# SCH_RoboFootball_2024-06-07.net
KiCad netlist of a schematic drawn in EasyEDA
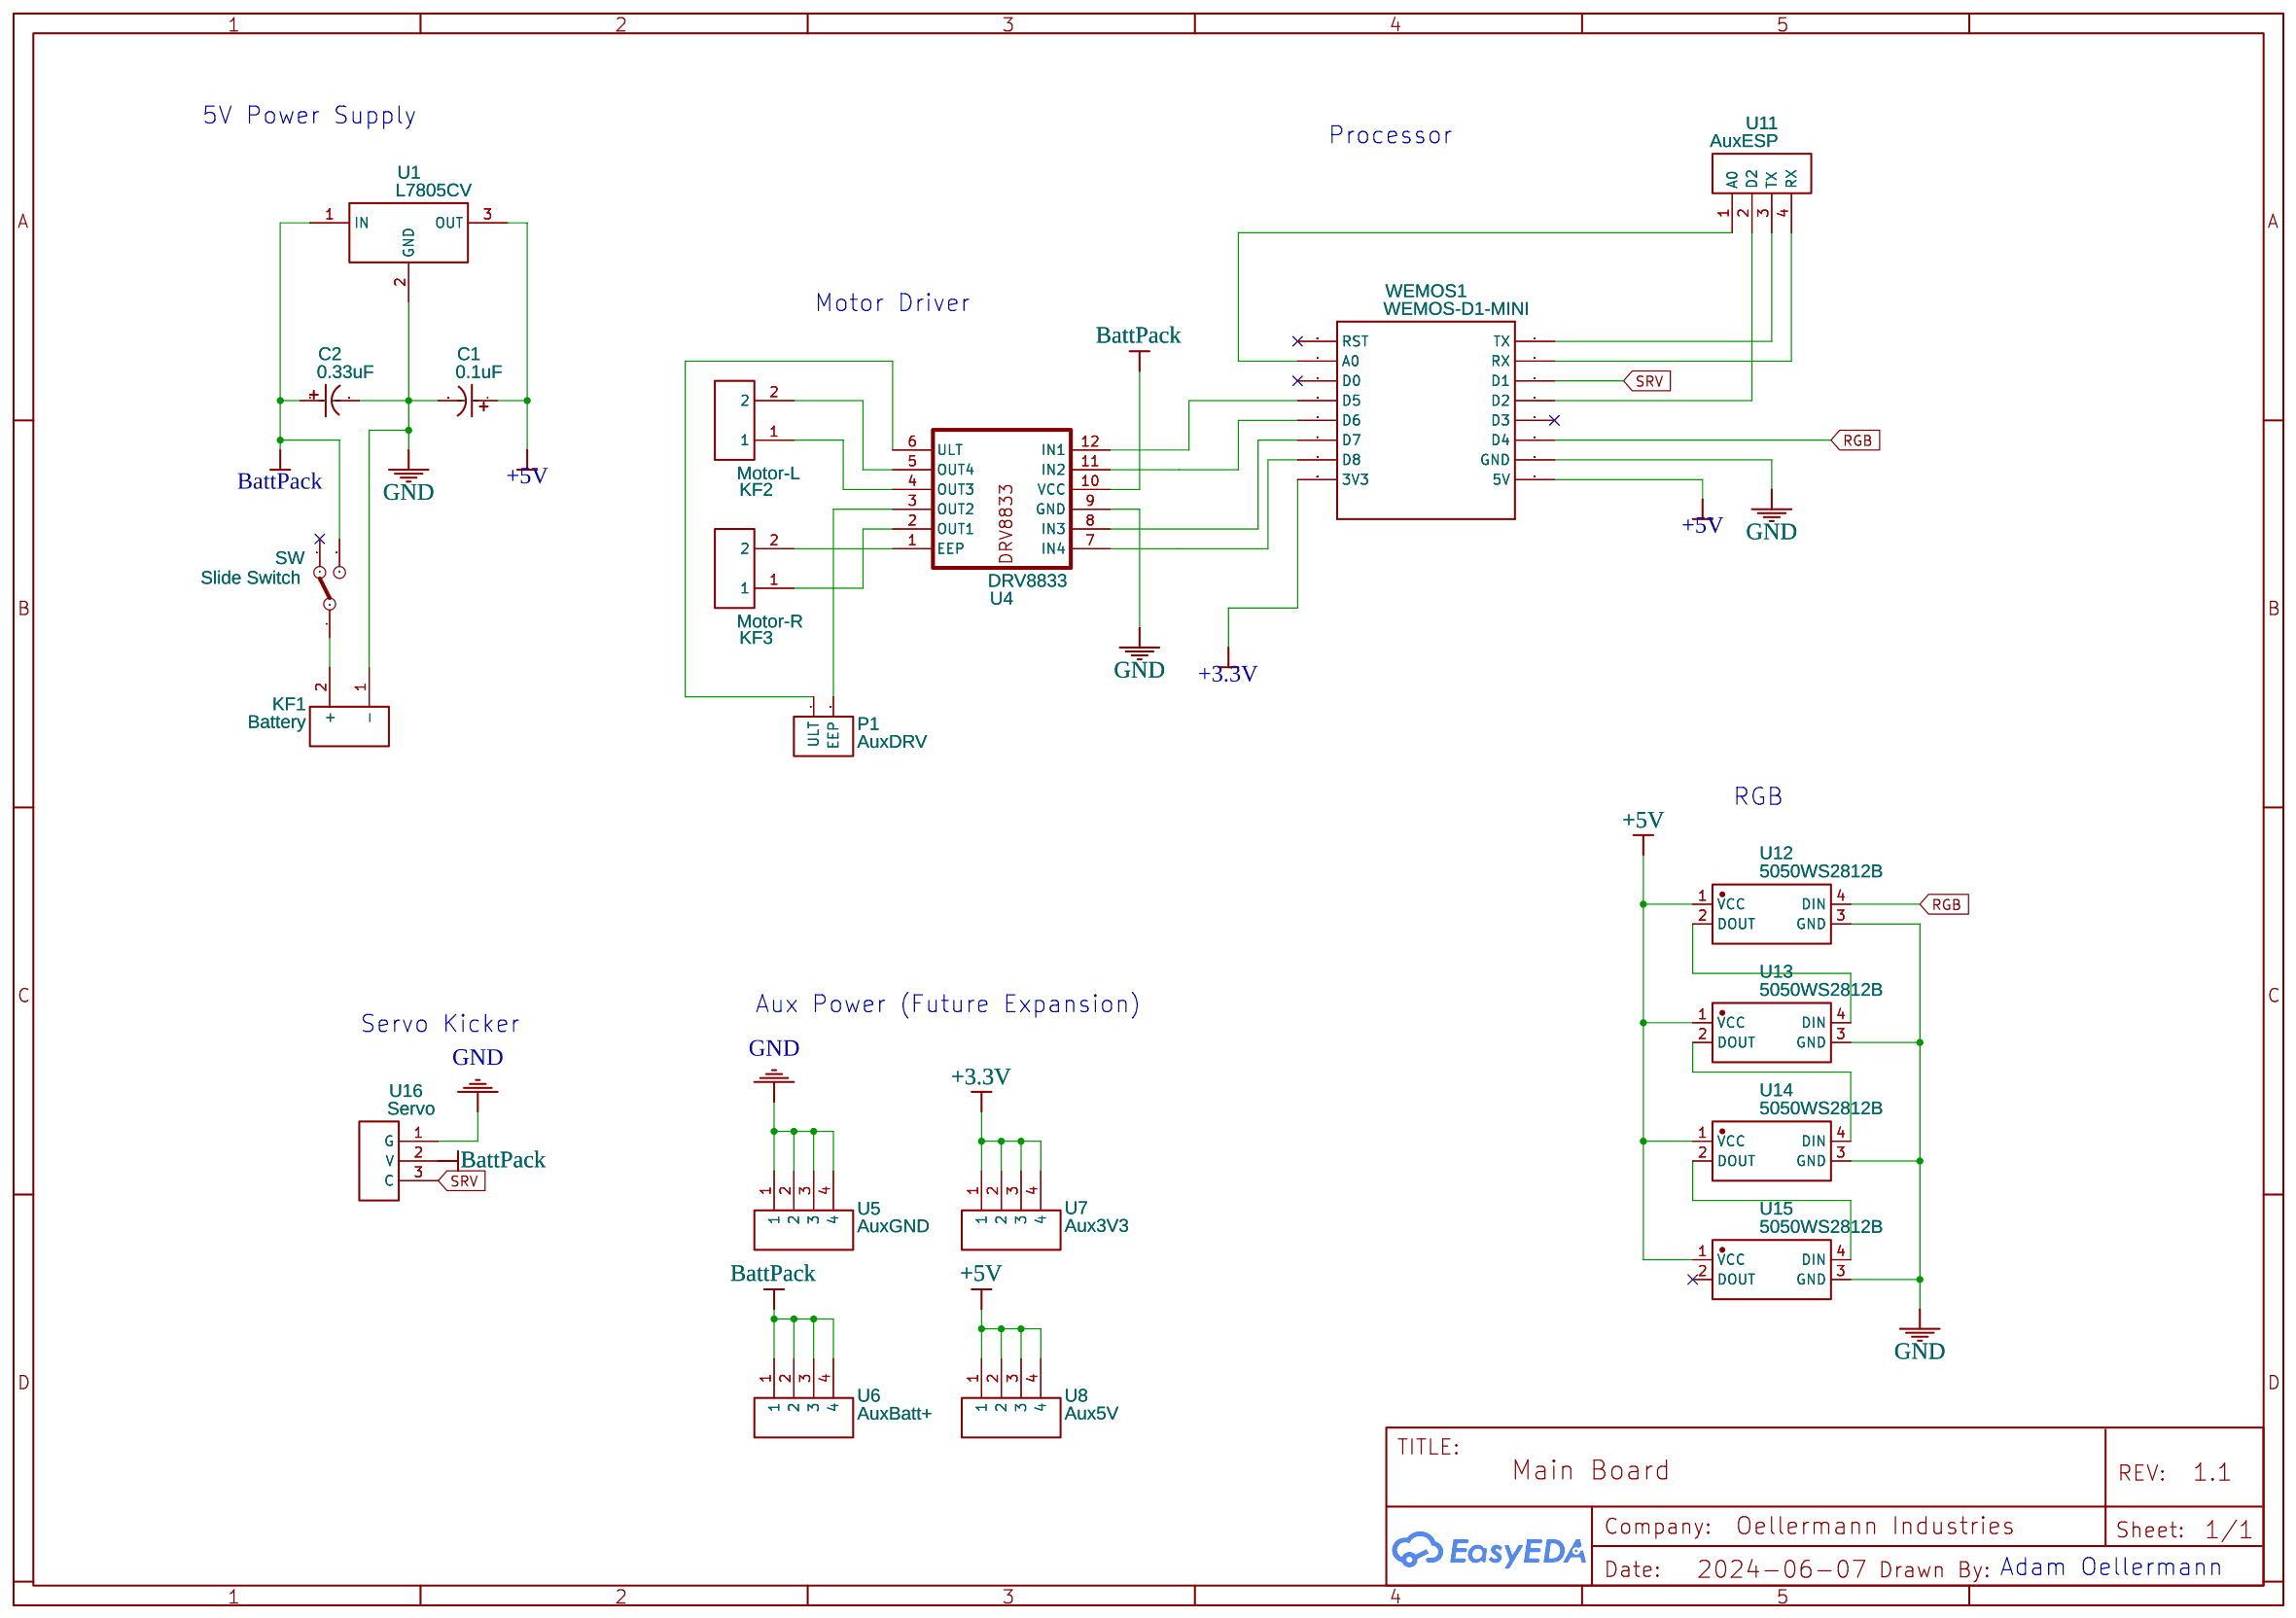
[diagram p0: schematic sheet]

(export (version "E")
  (design (tool "Eeschema 10.0.6"))
  (components
    (comp (ref "C1")
      (value "0.1uF")
      (fields
        (field (name "BOM_Manufacturer Part") "0.1uF 50V 4*7")
        (field (name "BOM_Supplier Part") "C45664")
      )
      (libsource (lib "") (part "0.1uF 50V 4*7"))
    )
    (comp (ref "C2")
      (value "0.33uF")
      (fields
        (field (name "BOM_Manufacturer Part") "0.33uF 50V 4*7")
        (field (name "BOM_Supplier Part") "C47875")
      )
      (libsource (lib "") (part "0.33uF 50V 4*7"))
    )
    (comp (ref "KF1") (value "Battery") (libsource (lib "") (part "K-301-2P")))
    (comp (ref "KF2") (value "Motor-L") (libsource (lib "") (part "K-301-2P_1")))
    (comp (ref "KF3") (value "Motor-R") (libsource (lib "") (part "K-301-2P_1")))
    (comp (ref "P1")
      (value "AuxDRV")
      (fields
        (field (name "BOM_Manufacturer Part") "2.54-1*2PFemale")
        (field (name "BOM_Supplier Part") "C49661")
      )
      (libsource (lib "") (part "Header-Female-2.54_1x2"))
    )
    (comp (ref "SW")
      (value "Slide Switch")
      (fields (field (name "BOM_Manufacturer Part") "Switch SPDT"))
      (libsource (lib "") (part "Slide Switch"))
    )
    (comp (ref "U1")
      (value "L7805CV")
      (fields (field (name "BOM_Supplier Part") "C111887"))
      (libsource (lib "") (part "L7805CV"))
    )
    (comp (ref "U4") (value "DRV8833") (libsource (lib "") (part "DRV8833 (NO ORIGINAL)")))
    (comp (ref "U5")
      (value "AuxGND")
      (fields (field (name "BOM_Supplier Part") "undefined"))
      (libsource (lib "") (part "PINHEADER1X4"))
    )
    (comp (ref "U6")
      (value "AuxBatt+")
      (fields (field (name "BOM_Supplier Part") "undefined"))
      (libsource (lib "") (part "PINHEADER1X4"))
    )
    (comp (ref "U7")
      (value "Aux3V3")
      (fields (field (name "BOM_Supplier Part") "undefined"))
      (libsource (lib "") (part "PINHEADER1X4"))
    )
    (comp (ref "U8")
      (value "Aux5V")
      (fields (field (name "BOM_Supplier Part") "undefined"))
      (libsource (lib "") (part "PINHEADER1X4"))
    )
    (comp (ref "U11")
      (value "AuxESP")
      (fields (field (name "BOM_Supplier Part") "undefined"))
      (libsource (lib "") (part "PINHEADER1X4_1"))
    )
    (comp (ref "U12")
      (value "5050WS2812B")
      (fields (field (name "BOM_Supplier Part") "C2874876"))
      (libsource (lib "") (part "5050WS2812B"))
    )
    (comp (ref "U13")
      (value "5050WS2812B")
      (fields (field (name "BOM_Supplier Part") "C2874876"))
      (libsource (lib "") (part "5050WS2812B"))
    )
    (comp (ref "U14")
      (value "5050WS2812B")
      (fields (field (name "BOM_Supplier Part") "C2874876"))
      (libsource (lib "") (part "5050WS2812B"))
    )
    (comp (ref "U15")
      (value "5050WS2812B")
      (fields (field (name "BOM_Supplier Part") "C2874876"))
      (libsource (lib "") (part "5050WS2812B"))
    )
    (comp (ref "U16")
      (value "Servo")
      (fields (field (name "BOM_Manufacturer Part") "Pin_Header_2"))
      (libsource (lib "") (part "PINHEADER1X3"))
    )
    (comp (ref "WEMOS1") (value "WEMOS-D1-MINI") (libsource (lib "") (part "WEMOS-D1-MINI")))
  )
  (nets
    (net (code "1") (name "+3.3V") (class "Default")
      (node (ref "U7") (pin "1") (pinfunction "1_1") (pintype "unspecified"))
      (node (ref "U7") (pin "2") (pinfunction "2_2") (pintype "unspecified"))
      (node (ref "U7") (pin "3") (pinfunction "3_3") (pintype "unspecified"))
      (node (ref "U7") (pin "4") (pinfunction "4_4") (pintype "unspecified"))
      (node (ref "WEMOS1") (pin "3V3") (pinfunction "3V3_3V3") (pintype "unspecified"))
    )
    (net (code "2") (name "+5V") (class "Default")
      (node (ref "C1") (pin "1") (pinfunction "1_1") (pintype "input"))
      (node (ref "U1") (pin "3") (pinfunction "OUT_3") (pintype "passive"))
      (node (ref "U12") (pin "1") (pinfunction "VCC_1") (pintype "unspecified"))
      (node (ref "U13") (pin "1") (pinfunction "VCC_1") (pintype "unspecified"))
      (node (ref "U14") (pin "1") (pinfunction "VCC_1") (pintype "unspecified"))
      (node (ref "U15") (pin "1") (pinfunction "VCC_1") (pintype "unspecified"))
      (node (ref "U8") (pin "1") (pinfunction "1_1") (pintype "unspecified"))
      (node (ref "U8") (pin "2") (pinfunction "2_2") (pintype "unspecified"))
      (node (ref "U8") (pin "3") (pinfunction "3_3") (pintype "unspecified"))
      (node (ref "U8") (pin "4") (pinfunction "4_4") (pintype "unspecified"))
      (node (ref "WEMOS1") (pin "5V") (pinfunction "5V_5V") (pintype "unspecified"))
    )
    (net (code "3") (name "BattPack") (class "Default")
      (node (ref "C2") (pin "1") (pinfunction "1_1") (pintype "input"))
      (node (ref "SW") (pin "3") (pinfunction "NO_3") (pintype "unspecified"))
      (node (ref "U1") (pin "1") (pinfunction "IN_1") (pintype "passive"))
      (node (ref "U16") (pin "2") (pinfunction "V_2") (pintype "unspecified"))
      (node (ref "U4") (pin "10") (pinfunction "VCC_10") (pintype "unspecified"))
      (node (ref "U6") (pin "1") (pinfunction "1_1") (pintype "unspecified"))
      (node (ref "U6") (pin "2") (pinfunction "2_2") (pintype "unspecified"))
      (node (ref "U6") (pin "3") (pinfunction "3_3") (pintype "unspecified"))
      (node (ref "U6") (pin "4") (pinfunction "4_4") (pintype "unspecified"))
    )
    (net (code "4") (name "GND") (class "Default")
      (node (ref "C1") (pin "2") (pinfunction "2_2") (pintype "input"))
      (node (ref "C2") (pin "2") (pinfunction "2_2") (pintype "input"))
      (node (ref "KF1") (pin "1") (pinfunction "-_1") (pintype "unspecified"))
      (node (ref "U1") (pin "2") (pinfunction "GND_2") (pintype "passive"))
      (node (ref "U12") (pin "3") (pinfunction "GND_3") (pintype "unspecified"))
      (node (ref "U13") (pin "3") (pinfunction "GND_3") (pintype "unspecified"))
      (node (ref "U14") (pin "3") (pinfunction "GND_3") (pintype "unspecified"))
      (node (ref "U15") (pin "3") (pinfunction "GND_3") (pintype "unspecified"))
      (node (ref "U16") (pin "1") (pinfunction "G_1") (pintype "unspecified"))
      (node (ref "U4") (pin "9") (pinfunction "GND_9") (pintype "unspecified"))
      (node (ref "U5") (pin "1") (pinfunction "1_1") (pintype "unspecified"))
      (node (ref "U5") (pin "2") (pinfunction "2_2") (pintype "unspecified"))
      (node (ref "U5") (pin "3") (pinfunction "3_3") (pintype "unspecified"))
      (node (ref "U5") (pin "4") (pinfunction "4_4") (pintype "unspecified"))
      (node (ref "WEMOS1") (pin "GND") (pinfunction "GND_GND") (pintype "unspecified"))
    )
    (net (code "5") (name "Net-(KF1-+)") (class "Default")
      (node (ref "KF1") (pin "2") (pinfunction "+_2") (pintype "unspecified"))
      (node (ref "SW") (pin "1") (pinfunction "NC_1") (pintype "unspecified"))
    )
    (net (code "6") (name "Net-(P1-EEP)") (class "Default")
      (node (ref "KF3") (pin "2") (pinfunction "2_2") (pintype "unspecified"))
      (node (ref "P1") (pin "1") (pinfunction "EEP_1") (pintype "input"))
      (node (ref "U4") (pin "1") (pinfunction "EEP_1") (pintype "unspecified"))
      (node (ref "U4") (pin "3") (pinfunction "OUT2_3") (pintype "unspecified"))
    )
    (net (code "7") (name "Net-(P1-ULT)") (class "Default")
      (node (ref "P1") (pin "2") (pinfunction "ULT_2") (pintype "input"))
      (node (ref "U4") (pin "6") (pinfunction "ULT_6") (pintype "unspecified"))
    )
    (net (code "8") (name "Net-(U4-IN1)") (class "Default")
      (node (ref "U4") (pin "12") (pinfunction "IN1_12") (pintype "unspecified"))
      (node (ref "WEMOS1") (pin "D5") (pinfunction "D5_D5") (pintype "unspecified"))
    )
    (net (code "9") (name "Net-(U4-IN2)") (class "Default")
      (node (ref "U4") (pin "11") (pinfunction "IN2_11") (pintype "unspecified"))
      (node (ref "WEMOS1") (pin "D6") (pinfunction "D6_D6") (pintype "unspecified"))
    )
    (net (code "10") (name "Net-(U4-IN3)") (class "Default")
      (node (ref "U4") (pin "8") (pinfunction "IN3_8") (pintype "unspecified"))
      (node (ref "WEMOS1") (pin "D7") (pinfunction "D7_D7") (pintype "unspecified"))
    )
    (net (code "11") (name "Net-(U4-IN4)") (class "Default")
      (node (ref "U4") (pin "7") (pinfunction "IN4_7") (pintype "unspecified"))
      (node (ref "WEMOS1") (pin "D8") (pinfunction "D8_D8") (pintype "unspecified"))
    )
    (net (code "12") (name "Net-(U4-OUT1)") (class "Default")
      (node (ref "KF3") (pin "1") (pinfunction "1_1") (pintype "unspecified"))
      (node (ref "U4") (pin "2") (pinfunction "OUT1_2") (pintype "unspecified"))
    )
    (net (code "13") (name "Net-(U4-OUT3)") (class "Default")
      (node (ref "KF2") (pin "1") (pinfunction "1_1") (pintype "unspecified"))
      (node (ref "U4") (pin "4") (pinfunction "OUT3_4") (pintype "unspecified"))
    )
    (net (code "14") (name "Net-(U4-OUT4)") (class "Default")
      (node (ref "KF2") (pin "2") (pinfunction "2_2") (pintype "unspecified"))
      (node (ref "U4") (pin "5") (pinfunction "OUT4_5") (pintype "unspecified"))
    )
    (net (code "15") (name "Net-(U11-A0)") (class "Default")
      (node (ref "U11") (pin "1") (pinfunction "A0_1") (pintype "unspecified"))
      (node (ref "WEMOS1") (pin "A0") (pinfunction "A0_A0") (pintype "unspecified"))
    )
    (net (code "16") (name "Net-(U11-D2)") (class "Default")
      (node (ref "U11") (pin "2") (pinfunction "D2_2") (pintype "unspecified"))
      (node (ref "WEMOS1") (pin "D2") (pinfunction "D2_D2") (pintype "unspecified"))
    )
    (net (code "17") (name "Net-(U11-RX)") (class "Default")
      (node (ref "U11") (pin "4") (pinfunction "RX_4") (pintype "unspecified"))
      (node (ref "WEMOS1") (pin "RX") (pinfunction "RX_RX") (pintype "unspecified"))
    )
    (net (code "18") (name "Net-(U11-TX)") (class "Default")
      (node (ref "U11") (pin "3") (pinfunction "TX_3") (pintype "unspecified"))
      (node (ref "WEMOS1") (pin "TX") (pinfunction "TX_TX") (pintype "unspecified"))
    )
    (net (code "19") (name "Net-(U12-DOUT)") (class "Default")
      (node (ref "U12") (pin "2") (pinfunction "DOUT_2") (pintype "unspecified"))
      (node (ref "U13") (pin "4") (pinfunction "DIN_4") (pintype "unspecified"))
    )
    (net (code "20") (name "Net-(U13-DOUT)") (class "Default")
      (node (ref "U13") (pin "2") (pinfunction "DOUT_2") (pintype "unspecified"))
      (node (ref "U14") (pin "4") (pinfunction "DIN_4") (pintype "unspecified"))
    )
    (net (code "21") (name "Net-(U14-DOUT)") (class "Default")
      (node (ref "U14") (pin "2") (pinfunction "DOUT_2") (pintype "unspecified"))
      (node (ref "U15") (pin "4") (pinfunction "DIN_4") (pintype "unspecified"))
    )
    (net (code "22") (name "RGB") (class "Default")
      (node (ref "U12") (pin "4") (pinfunction "DIN_4") (pintype "unspecified"))
      (node (ref "WEMOS1") (pin "D4") (pinfunction "D4_D4") (pintype "unspecified"))
    )
    (net (code "23") (name "SRV") (class "Default")
      (node (ref "U16") (pin "3") (pinfunction "C_3") (pintype "unspecified"))
      (node (ref "WEMOS1") (pin "D1") (pinfunction "D1_D1") (pintype "unspecified"))
    )
    (net (code "24") (name "unconnected-(SW-C-Pad2)") (class "Default")
      (node (ref "SW") (pin "2") (pinfunction "C_2") (pintype "unspecified+no_connect"))
    )
    (net (code "25") (name "unconnected-(U15-DOUT-Pad2)") (class "Default")
      (node (ref "U15") (pin "2") (pinfunction "DOUT_2") (pintype "unspecified+no_connect"))
    )
    (net (code "26") (name "unconnected-(WEMOS1-PadD0)") (class "Default")
      (node (ref "WEMOS1") (pin "D0") (pinfunction "D0_D0") (pintype "unspecified+no_connect"))
    )
    (net (code "27") (name "unconnected-(WEMOS1-PadD3)") (class "Default")
      (node (ref "WEMOS1") (pin "D3") (pinfunction "D3_D3") (pintype "unspecified+no_connect"))
    )
    (net (code "28") (name "unconnected-(WEMOS1-PadRST)") (class "Default")
      (node (ref "WEMOS1") (pin "RST") (pinfunction "RST_RST") (pintype "unspecified+no_connect"))
    )
  )
)
